# SHT2x_breakout.net
KiCad netlist of a schematic drawn in EAGLE
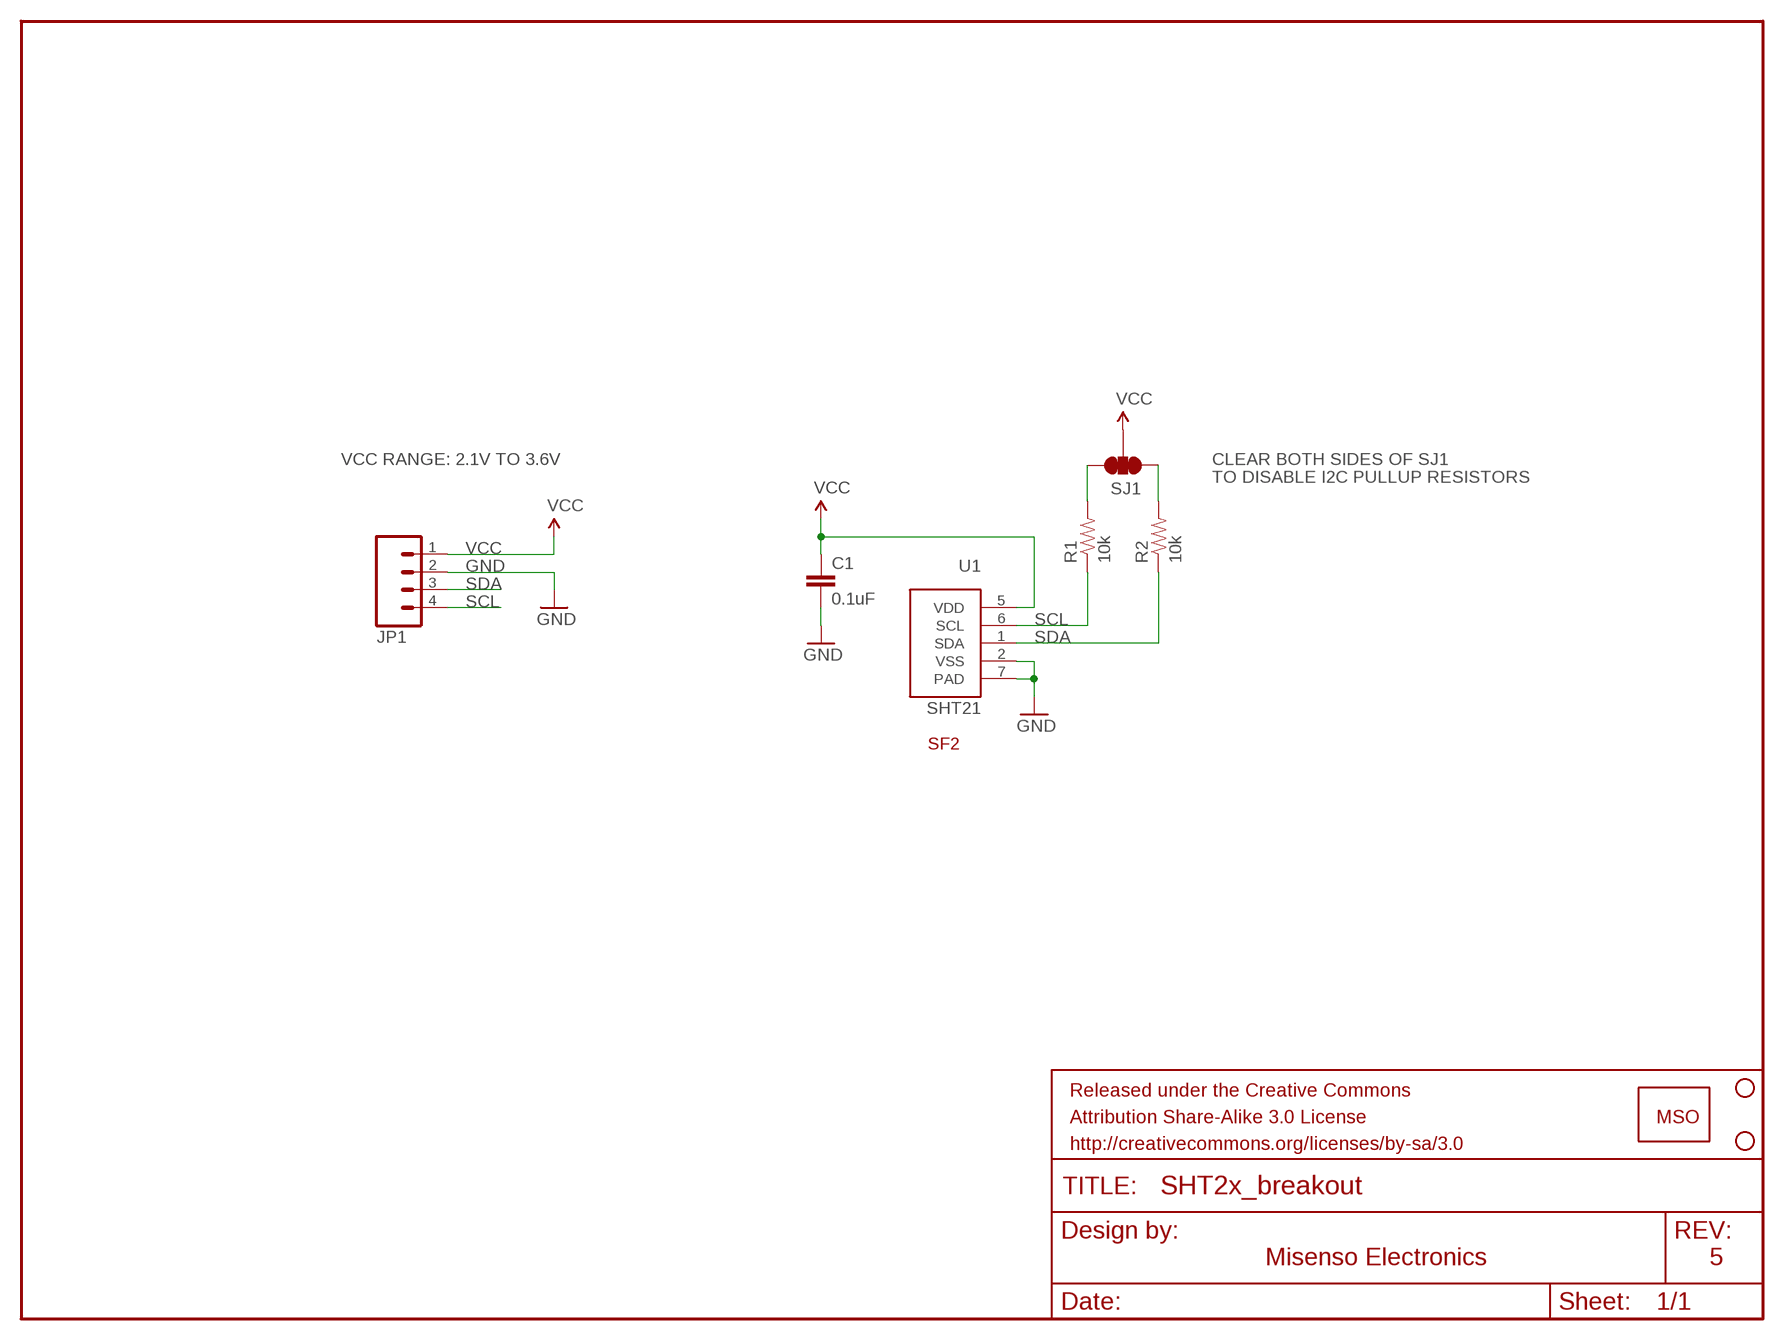
[diagram p0: schematic, sheet 1]

(export (version "E")
  (design (tool "Eeschema 10.0.6"))
  (components
    (comp (ref "C1")
      (value "0.1uF")
      (footprint "eagle-import:0402-CAP")
      (libsource (lib "eagle-import") (part "CAP0402-CAP"))
    )
    (comp (ref "JP1")
      (value "M04PTH")
      (footprint "eagle-import:1X04")
      (libsource (lib "eagle-import") (part "M04PTH"))
    )
    (comp (ref "R1")
      (value "10k")
      (footprint "eagle-import:0402-RES")
      (libsource (lib "eagle-import") (part "RESISTOR0402-RES"))
    )
    (comp (ref "R2")
      (value "10k")
      (footprint "eagle-import:0402-RES")
      (libsource (lib "eagle-import") (part "RESISTOR0402-RES"))
    )
    (comp (ref "SJ1")
      (value "SOLDERJUMPER_2WAYPASTE1&2&3")
      (footprint "eagle-import:SJ_3_PASTE1&2&3")
      (libsource (lib "eagle-import") (part "SOLDERJUMPER_2WAYPASTE1&2&3"))
    )
    (comp (ref "STANDOFF1")
      (value "STAND-OFF")
      (footprint "eagle-import:STAND-OFF")
      (libsource (lib "eagle-import") (part "STAND-OFF"))
    )
    (comp (ref "STANDOFF2")
      (value "STAND-OFF")
      (footprint "eagle-import:STAND-OFF")
      (libsource (lib "eagle-import") (part "STAND-OFF"))
    )
    (comp (ref "U$2")
      (value "MSO-LOGO")
      (footprint "eagle-import:MSO-LOGO")
      (libsource (lib "eagle-import") (part "MSO-LOGO"))
    )
    (comp (ref "U$3")
      (value "MISC-SENSIRION-SF2")
      (footprint "eagle-import:MISC-SENSIRION-SF2")
      (libsource (lib "eagle-import") (part "MISC-SENSIRION-SF2"))
    )
    (comp (ref "U1")
      (value "SHT21")
      (footprint "eagle-import:SEN-SENSIRION-SHT2X")
      (libsource (lib "eagle-import") (part "SEN-SENSIRION-SHT2X"))
    )
  )
  (nets
    (net (code "1") (name "/SCL") (class "Default")
      (node (ref "JP1") (pin "4") (pinfunction "4_4") (pintype "passive"))
      (node (ref "R1") (pin "1") (pinfunction "1_1") (pintype "passive"))
      (node (ref "U1") (pin "6") (pinfunction "SCL_6") (pintype "bidirectional"))
    )
    (net (code "2") (name "/SDA") (class "Default")
      (node (ref "JP1") (pin "3") (pinfunction "3_3") (pintype "passive"))
      (node (ref "R2") (pin "1") (pinfunction "1_1") (pintype "passive"))
      (node (ref "U1") (pin "1") (pinfunction "SDA_1") (pintype "bidirectional"))
    )
    (net (code "3") (name "GND") (class "Default")
      (node (ref "C1") (pin "2") (pinfunction "2_2") (pintype "passive"))
      (node (ref "JP1") (pin "2") (pinfunction "2_2") (pintype "passive"))
      (node (ref "U1") (pin "2") (pinfunction "VSS_2") (pintype "bidirectional"))
      (node (ref "U1") (pin "7") (pinfunction "PAD_7") (pintype "bidirectional"))
    )
    (net (code "4") (name "Net-(R1-Pad2)") (class "Default")
      (node (ref "R1") (pin "2") (pinfunction "2_2") (pintype "passive"))
      (node (ref "SJ1") (pin "3") (pinfunction "3_3") (pintype "passive"))
    )
    (net (code "5") (name "Net-(R2-Pad2)") (class "Default")
      (node (ref "R2") (pin "2") (pinfunction "2_2") (pintype "passive"))
      (node (ref "SJ1") (pin "1") (pinfunction "1_1") (pintype "passive"))
    )
    (net (code "6") (name "VCC") (class "Default")
      (node (ref "C1") (pin "1") (pinfunction "1_1") (pintype "passive"))
      (node (ref "JP1") (pin "1") (pinfunction "1_1") (pintype "passive"))
      (node (ref "SJ1") (pin "2") (pinfunction "2_2") (pintype "passive"))
      (node (ref "U1") (pin "5") (pinfunction "VDD_5") (pintype "bidirectional"))
    )
  )
)
